# misc.net
KiCad netlist of a schematic drawn in Altium Designer
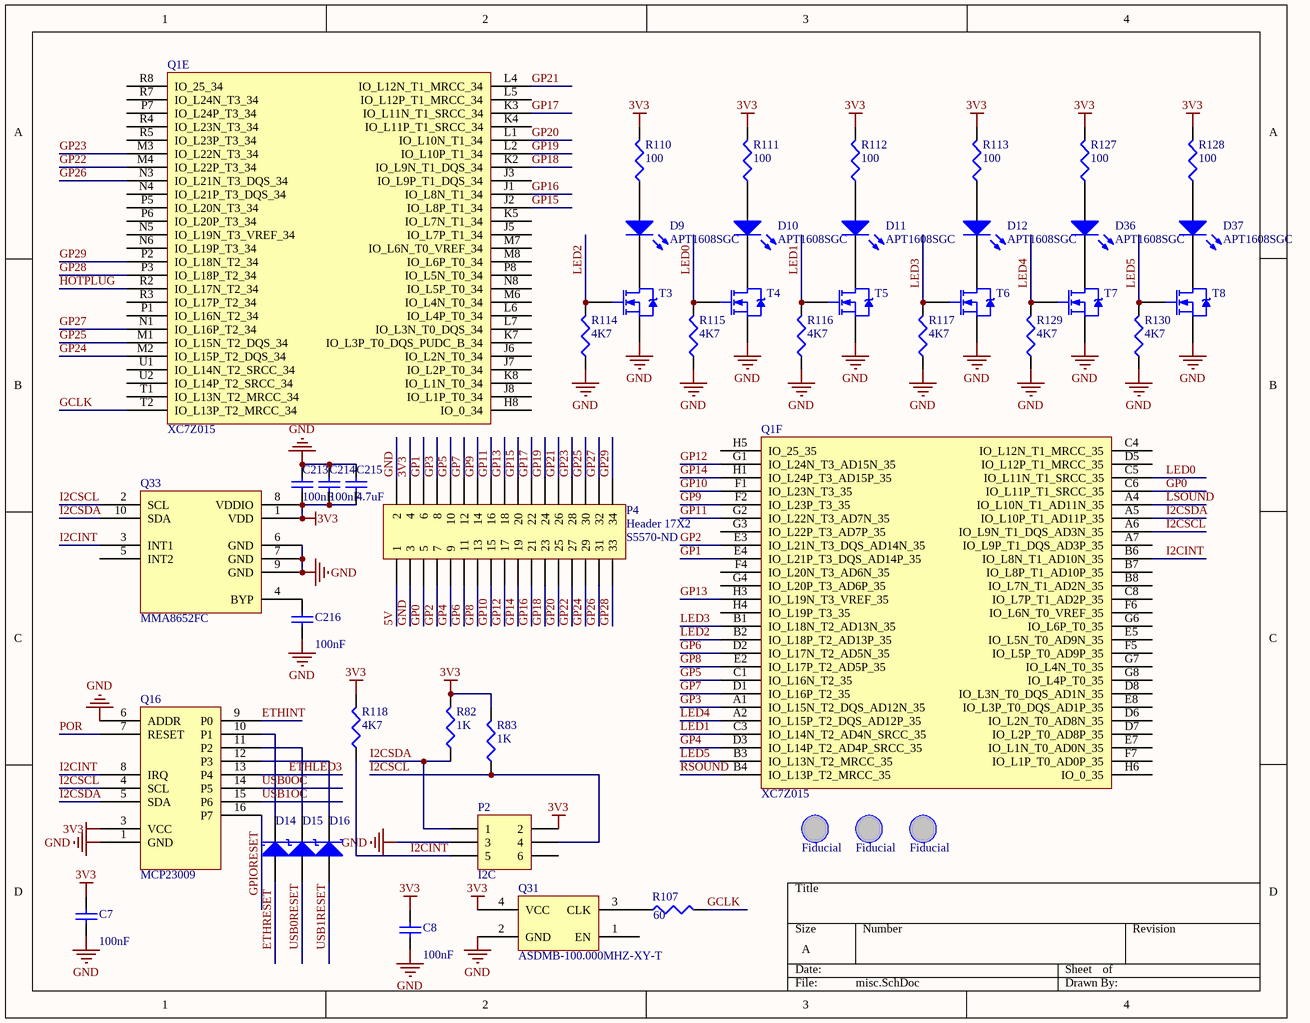
[diagram p0: misc.SchDoc]

(export (version "E")
  (design (tool "Eeschema 10.0.6"))
  (components
    (comp (ref "C7")
      (value "100nF")
      (footprint "CAPC1005X06L")
      (description "Capacitor")
      (fields (field (name "Comment") "Cap") (field (name "PUBLISHER") "Altium Limited"))
      (libsource (lib "Miscellaneous Devices") (part "Cap"))
    )
    (comp (ref "C8")
      (value "100nF")
      (footprint "CAPC1005X06L")
      (description "Capacitor")
      (fields (field (name "Comment") "Cap") (field (name "PUBLISHER") "Altium Limited"))
      (libsource (lib "Miscellaneous Devices") (part "Cap"))
    )
    (comp (ref "C213")
      (value "100nF")
      (footprint "CAPC1005X06L")
      (description "Capacitor")
      (fields (field (name "Comment") "Cap") (field (name "PUBLISHER") "Altium Limited"))
      (libsource (lib "Miscellaneous Devices") (part "Cap"))
    )
    (comp (ref "C214")
      (value "100nF")
      (footprint "CAPC1005X06L")
      (description "Capacitor")
      (fields (field (name "Comment") "Cap") (field (name "PUBLISHER") "Altium Limited"))
      (libsource (lib "Miscellaneous Devices") (part "Cap"))
    )
    (comp (ref "C215")
      (value "4.7uF")
      (footprint "CAPC1608X90N")
      (description "Capacitor")
      (fields (field (name "Comment") "GRM188R60J475ME19D") (field (name "PUBLISHER") "Altium Limited"))
      (libsource (lib "Miscellaneous Devices") (part "Cap"))
    )
    (comp (ref "C216")
      (value "100nF")
      (footprint "CAPC1005X06L")
      (description "Capacitor")
      (fields (field (name "Comment") "Cap") (field (name "PUBLISHER") "Altium Limited"))
      (libsource (lib "Miscellaneous Devices") (part "Cap"))
    )
    (comp (ref "D9")
      (value "APT1608SGC")
      (footprint "LED-0603")
      (description "Typical RED, GREEN, YELLOW, AMBER GaAs LED")
      (fields (field (name "PUBLISHER") "Altium Limited"))
      (libsource (lib "Miscellaneous Devices") (part "LED2"))
    )
    (comp (ref "D10")
      (value "APT1608SGC")
      (footprint "LED-0603")
      (description "Typical RED, GREEN, YELLOW, AMBER GaAs LED")
      (fields (field (name "PUBLISHER") "Altium Limited"))
      (libsource (lib "Miscellaneous Devices") (part "LED2"))
    )
    (comp (ref "D11")
      (value "APT1608SGC")
      (footprint "LED-0603")
      (description "Typical RED, GREEN, YELLOW, AMBER GaAs LED")
      (fields (field (name "PUBLISHER") "Altium Limited"))
      (libsource (lib "Miscellaneous Devices") (part "LED2"))
    )
    (comp (ref "D12")
      (value "APT1608SGC")
      (footprint "LED-0603")
      (description "Typical RED, GREEN, YELLOW, AMBER GaAs LED")
      (fields (field (name "PUBLISHER") "Altium Limited"))
      (libsource (lib "Miscellaneous Devices") (part "LED2"))
    )
    (comp (ref "D14")
      (value "BAT54FSCT-ND")
      (footprint "BAT54")
      (description "Schottky Diode")
      (fields (field (name "PUBLISHER") "Altium Limited"))
      (libsource (lib "Miscellaneous Devices") (part "D Schottky"))
    )
    (comp (ref "D15")
      (value "BAT54FSCT-ND")
      (footprint "BAT54")
      (description "Schottky Diode")
      (fields (field (name "PUBLISHER") "Altium Limited"))
      (libsource (lib "Miscellaneous Devices") (part "D Schottky"))
    )
    (comp (ref "D16")
      (value "BAT54FSCT-ND")
      (footprint "BAT54")
      (description "Schottky Diode")
      (fields (field (name "PUBLISHER") "Altium Limited"))
      (libsource (lib "Miscellaneous Devices") (part "D Schottky"))
    )
    (comp (ref "D36")
      (value "APT1608SGC")
      (footprint "LED-0603")
      (description "Typical RED, GREEN, YELLOW, AMBER GaAs LED")
      (fields (field (name "PUBLISHER") "Altium Limited"))
      (libsource (lib "Miscellaneous Devices") (part "LED2"))
    )
    (comp (ref "D37")
      (value "APT1608SGC")
      (footprint "LED-0603")
      (description "Typical RED, GREEN, YELLOW, AMBER GaAs LED")
      (fields (field (name "PUBLISHER") "Altium Limited"))
      (libsource (lib "Miscellaneous Devices") (part "LED2"))
    )
    (comp (ref "FIDU1") (value "Fiducial") (footprint "FIDU") (libsource (lib "schlib") (part "FIDU")))
    (comp (ref "FIDU2") (value "Fiducial") (footprint "FIDU") (libsource (lib "schlib") (part "FIDU")))
    (comp (ref "FIDU3") (value "Fiducial") (footprint "FIDU") (libsource (lib "schlib") (part "FIDU")))
    (comp (ref "P2")
      (value "I2C")
      (footprint "HDR2X3")
      (description "Header, 3-Pin, Dual row")
      (fields (field (name "PUBLISHER") "Altium Limited"))
      (libsource (lib "Miscellaneous Connectors") (part "Header 3X2"))
    )
    (comp (ref "P4")
      (value "Header 17X2")
      (footprint "HDR2X17")
      (description "Header, 17-Pin, Dual row")
      (fields (field (name "SUPPLIER PART NUMBER 1") "S5570-ND") (field (name "PUBLISHER") "Altium Limited"))
      (libsource (lib "Miscellaneous Connectors") (part "Header 17X2"))
    )
    (comp (ref "Q1") (value "XC7Z015") (footprint "BGA484x22") (libsource (lib "schlib") (part "XC7Z015")))
    (comp (ref "Q16") (value "MCP23009") (footprint "MCP23009") (libsource (lib "schlib") (part "MCP23009")))
    (comp (ref "Q31")
      (value "ASDMB-100.000MHZ-XY-T")
      (footprint "ASDMB")
      (libsource (lib "schlib") (part "osc"))
    )
    (comp (ref "Q33")
      (value "MMA8652FC")
      (footprint "MMA8653FC")
      (libsource (lib "schlib") (part "MMA8652FC"))
    )
    (comp (ref "R82")
      (value "1K")
      (footprint "J1-0603")
      (description "Resistor")
      (fields (field (name "Comment") "RC1608J102CS") (field (name "PUBLISHER") "Altium Limited"))
      (libsource (lib "Miscellaneous Devices") (part "Res3"))
    )
    (comp (ref "R83")
      (value "1K")
      (footprint "J1-0603")
      (description "Resistor")
      (fields (field (name "Comment") "RC1608J102CS") (field (name "PUBLISHER") "Altium Limited"))
      (libsource (lib "Miscellaneous Devices") (part "Res3"))
    )
    (comp (ref "R107")
      (value "60")
      (footprint "J1-0603")
      (description "Resistor")
      (fields (field (name "Comment") "RC1608F60R4CS"))
      (libsource (lib "Miscellaneous Devices") (part "Res3"))
    )
    (comp (ref "R110")
      (value "100")
      (footprint "J1-0603")
      (description "Resistor")
      (fields (field (name "Comment") "RC1608F101CS"))
      (libsource (lib "Miscellaneous Devices") (part "Res3"))
    )
    (comp (ref "R111")
      (value "100")
      (footprint "J1-0603")
      (description "Resistor")
      (fields (field (name "Comment") "RC1608F101CS"))
      (libsource (lib "Miscellaneous Devices") (part "Res3"))
    )
    (comp (ref "R112")
      (value "100")
      (footprint "J1-0603")
      (description "Resistor")
      (fields (field (name "Comment") "RC1608F101CS"))
      (libsource (lib "Miscellaneous Devices") (part "Res3"))
    )
    (comp (ref "R113")
      (value "100")
      (footprint "J1-0603")
      (description "Resistor")
      (fields (field (name "Comment") "RC1608F101CS"))
      (libsource (lib "Miscellaneous Devices") (part "Res3"))
    )
    (comp (ref "R114")
      (value "4K7")
      (footprint "J1-0603")
      (description "Resistor")
      (fields (field (name "Comment") "RC1608J472CS"))
      (libsource (lib "Miscellaneous Devices") (part "Res3"))
    )
    (comp (ref "R115")
      (value "4K7")
      (footprint "J1-0603")
      (description "Resistor")
      (fields (field (name "Comment") "RC1608J472CS"))
      (libsource (lib "Miscellaneous Devices") (part "Res3"))
    )
    (comp (ref "R116")
      (value "4K7")
      (footprint "J1-0603")
      (description "Resistor")
      (fields (field (name "Comment") "RC1608J472CS"))
      (libsource (lib "Miscellaneous Devices") (part "Res3"))
    )
    (comp (ref "R117")
      (value "4K7")
      (footprint "J1-0603")
      (description "Resistor")
      (fields (field (name "Comment") "RC1608J472CS"))
      (libsource (lib "Miscellaneous Devices") (part "Res3"))
    )
    (comp (ref "R118")
      (value "4K7")
      (footprint "J1-0603")
      (description "Resistor")
      (fields (field (name "Comment") "RC1608J472CS"))
      (libsource (lib "Miscellaneous Devices") (part "Res3"))
    )
    (comp (ref "R127")
      (value "100")
      (footprint "J1-0603")
      (description "Resistor")
      (fields (field (name "Comment") "RC1608F101CS"))
      (libsource (lib "Miscellaneous Devices") (part "Res3"))
    )
    (comp (ref "R128")
      (value "100")
      (footprint "J1-0603")
      (description "Resistor")
      (fields (field (name "Comment") "RC1608F101CS"))
      (libsource (lib "Miscellaneous Devices") (part "Res3"))
    )
    (comp (ref "R129")
      (value "4K7")
      (footprint "J1-0603")
      (description "Resistor")
      (fields (field (name "Comment") "RC1608J472CS"))
      (libsource (lib "Miscellaneous Devices") (part "Res3"))
    )
    (comp (ref "R130")
      (value "4K7")
      (footprint "J1-0603")
      (description "Resistor")
      (fields (field (name "Comment") "RC1608J472CS"))
      (libsource (lib "Miscellaneous Devices") (part "Res3"))
    )
    (comp (ref "T3")
      (value "~")
      (footprint "EMT3F")
      (description "N-Channel Power MOSFET")
      (fields (field (name "PUBLISHER") "Altium Limited"))
      (libsource (lib "Miscellaneous Devices") (part "NMOS-2"))
    )
    (comp (ref "T4")
      (value "~")
      (footprint "EMT3F")
      (description "N-Channel Power MOSFET")
      (fields (field (name "PUBLISHER") "Altium Limited"))
      (libsource (lib "Miscellaneous Devices") (part "NMOS-2"))
    )
    (comp (ref "T5")
      (value "~")
      (footprint "EMT3F")
      (description "N-Channel Power MOSFET")
      (fields (field (name "PUBLISHER") "Altium Limited"))
      (libsource (lib "Miscellaneous Devices") (part "NMOS-2"))
    )
    (comp (ref "T6")
      (value "~")
      (footprint "EMT3F")
      (description "N-Channel Power MOSFET")
      (fields (field (name "PUBLISHER") "Altium Limited"))
      (libsource (lib "Miscellaneous Devices") (part "NMOS-2"))
    )
    (comp (ref "T7")
      (value "~")
      (footprint "EMT3F")
      (description "N-Channel Power MOSFET")
      (fields (field (name "PUBLISHER") "Altium Limited"))
      (libsource (lib "Miscellaneous Devices") (part "NMOS-2"))
    )
    (comp (ref "T8")
      (value "~")
      (footprint "EMT3F")
      (description "N-Channel Power MOSFET")
      (fields (field (name "PUBLISHER") "Altium Limited"))
      (libsource (lib "Miscellaneous Devices") (part "NMOS-2"))
    )
  )
  (nets
    (net (code "1") (name "/5V") (class "Default")
      (node (ref "P4") (pin "1") (pinfunction "1_1") (pintype "passive"))
    )
    (net (code "2") (name "/ETHINT") (class "Default")
      (node (ref "Q16") (pin "9") (pinfunction "P0_9") (pintype "passive"))
    )
    (net (code "3") (name "/ETHLED3") (class "Default")
      (node (ref "Q16") (pin "13") (pinfunction "P4_13") (pintype "passive"))
    )
    (net (code "4") (name "/ETHRESET") (class "Default")
      (node (ref "D14") (pin "1") (pinfunction "A_1") (pintype "passive"))
    )
    (net (code "5") (name "/GCLK") (class "Default")
      (node (ref "Q1") (pin "T2") (pinfunction "IO_L13P_T2_MRCC_34_T2") (pintype "passive"))
      (node (ref "R107") (pin "2") (pinfunction "2_2") (pintype "passive"))
    )
    (net (code "6") (name "/GP0") (class "Default")
      (node (ref "P4") (pin "5") (pinfunction "5_5") (pintype "passive"))
      (node (ref "Q1") (pin "C6") (pinfunction "IO_L11P_T1_SRCC_35_C6") (pintype "passive"))
    )
    (net (code "7") (name "/GP1") (class "Default")
      (node (ref "P4") (pin "6") (pinfunction "6_6") (pintype "passive"))
      (node (ref "Q1") (pin "E4") (pinfunction "IO_L21P_T3_DQS_AD14P_35_E4") (pintype "passive"))
    )
    (net (code "8") (name "/GP2") (class "Default")
      (node (ref "P4") (pin "7") (pinfunction "7_7") (pintype "passive"))
      (node (ref "Q1") (pin "E3") (pinfunction "IO_L21N_T3_DQS_AD14N_35_E3") (pintype "passive"))
    )
    (net (code "9") (name "/GP3") (class "Default")
      (node (ref "P4") (pin "8") (pinfunction "8_8") (pintype "passive"))
      (node (ref "Q1") (pin "A1") (pinfunction "IO_L15N_T2_DQS_AD12N_35_A1") (pintype "passive"))
    )
    (net (code "10") (name "/GP4") (class "Default")
      (node (ref "P4") (pin "9") (pinfunction "9_9") (pintype "passive"))
      (node (ref "Q1") (pin "D3") (pinfunction "IO_L14P_T2_AD4P_SRCC_35_D3") (pintype "passive"))
    )
    (net (code "11") (name "/GP5") (class "Default")
      (node (ref "P4") (pin "10") (pinfunction "10_10") (pintype "passive"))
      (node (ref "Q1") (pin "C1") (pinfunction "IO_L16N_T2_35_C1") (pintype "passive"))
    )
    (net (code "12") (name "/GP6") (class "Default")
      (node (ref "P4") (pin "11") (pinfunction "11_11") (pintype "passive"))
      (node (ref "Q1") (pin "D2") (pinfunction "IO_L17N_T2_AD5N_35_D2") (pintype "passive"))
    )
    (net (code "13") (name "/GP7") (class "Default")
      (node (ref "P4") (pin "12") (pinfunction "12_12") (pintype "passive"))
      (node (ref "Q1") (pin "D1") (pinfunction "IO_L16P_T2_35_D1") (pintype "passive"))
    )
    (net (code "14") (name "/GP8") (class "Default")
      (node (ref "P4") (pin "13") (pinfunction "13_13") (pintype "passive"))
      (node (ref "Q1") (pin "E2") (pinfunction "IO_L17P_T2_AD5P_35_E2") (pintype "passive"))
    )
    (net (code "15") (name "/GP9") (class "Default")
      (node (ref "P4") (pin "14") (pinfunction "14_14") (pintype "passive"))
      (node (ref "Q1") (pin "F2") (pinfunction "IO_L23P_T3_35_F2") (pintype "passive"))
    )
    (net (code "16") (name "/GP10") (class "Default")
      (node (ref "P4") (pin "15") (pinfunction "15_15") (pintype "passive"))
      (node (ref "Q1") (pin "F1") (pinfunction "IO_L23N_T3_35_F1") (pintype "passive"))
    )
    (net (code "17") (name "/GP11") (class "Default")
      (node (ref "P4") (pin "16") (pinfunction "16_16") (pintype "passive"))
      (node (ref "Q1") (pin "G2") (pinfunction "IO_L22N_T3_AD7N_35_G2") (pintype "passive"))
    )
    (net (code "18") (name "/GP12") (class "Default")
      (node (ref "P4") (pin "17") (pinfunction "17_17") (pintype "passive"))
      (node (ref "Q1") (pin "G1") (pinfunction "IO_L24N_T3_AD15N_35_G1") (pintype "passive"))
    )
    (net (code "19") (name "/GP13") (class "Default")
      (node (ref "P4") (pin "18") (pinfunction "18_18") (pintype "passive"))
      (node (ref "Q1") (pin "H3") (pinfunction "IO_L19N_T3_VREF_35_H3") (pintype "passive"))
    )
    (net (code "20") (name "/GP14") (class "Default")
      (node (ref "P4") (pin "19") (pinfunction "19_19") (pintype "passive"))
      (node (ref "Q1") (pin "H1") (pinfunction "IO_L24P_T3_AD15P_35_H1") (pintype "passive"))
    )
    (net (code "21") (name "/GP15") (class "Default")
      (node (ref "P4") (pin "20") (pinfunction "20_20") (pintype "passive"))
      (node (ref "Q1") (pin "J2") (pinfunction "IO_L8P_T1_34_J2") (pintype "passive"))
    )
    (net (code "22") (name "/GP16") (class "Default")
      (node (ref "P4") (pin "21") (pinfunction "21_21") (pintype "passive"))
      (node (ref "Q1") (pin "J1") (pinfunction "IO_L8N_T1_34_J1") (pintype "passive"))
    )
    (net (code "23") (name "/GP17") (class "Default")
      (node (ref "P4") (pin "22") (pinfunction "22_22") (pintype "passive"))
      (node (ref "Q1") (pin "K3") (pinfunction "IO_L11N_T1_SRCC_34_K3") (pintype "passive"))
    )
    (net (code "24") (name "/GP18") (class "Default")
      (node (ref "P4") (pin "23") (pinfunction "23_23") (pintype "passive"))
      (node (ref "Q1") (pin "K2") (pinfunction "IO_L9N_T1_DQS_34_K2") (pintype "passive"))
    )
    (net (code "25") (name "/GP19") (class "Default")
      (node (ref "P4") (pin "24") (pinfunction "24_24") (pintype "passive"))
      (node (ref "Q1") (pin "L2") (pinfunction "IO_L10P_T1_34_L2") (pintype "passive"))
    )
    (net (code "26") (name "/GP20") (class "Default")
      (node (ref "P4") (pin "25") (pinfunction "25_25") (pintype "passive"))
      (node (ref "Q1") (pin "L1") (pinfunction "IO_L10N_T1_34_L1") (pintype "passive"))
    )
    (net (code "27") (name "/GP21") (class "Default")
      (node (ref "P4") (pin "26") (pinfunction "26_26") (pintype "passive"))
      (node (ref "Q1") (pin "L4") (pinfunction "IO_L12N_T1_MRCC_34_L4") (pintype "passive"))
    )
    (net (code "28") (name "/GP22") (class "Default")
      (node (ref "P4") (pin "27") (pinfunction "27_27") (pintype "passive"))
      (node (ref "Q1") (pin "M4") (pinfunction "IO_L22P_T3_34_M4") (pintype "passive"))
    )
    (net (code "29") (name "/GP23") (class "Default")
      (node (ref "P4") (pin "28") (pinfunction "28_28") (pintype "passive"))
      (node (ref "Q1") (pin "M3") (pinfunction "IO_L22N_T3_34_M3") (pintype "passive"))
    )
    (net (code "30") (name "/GP24") (class "Default")
      (node (ref "P4") (pin "29") (pinfunction "29_29") (pintype "passive"))
      (node (ref "Q1") (pin "M2") (pinfunction "IO_L15P_T2_DQS_34_M2") (pintype "passive"))
    )
    (net (code "31") (name "/GP25") (class "Default")
      (node (ref "P4") (pin "30") (pinfunction "30_30") (pintype "passive"))
      (node (ref "Q1") (pin "M1") (pinfunction "IO_L15N_T2_DQS_34_M1") (pintype "passive"))
    )
    (net (code "32") (name "/GP26") (class "Default")
      (node (ref "P4") (pin "31") (pinfunction "31_31") (pintype "passive"))
      (node (ref "Q1") (pin "N3") (pinfunction "IO_L21N_T3_DQS_34_N3") (pintype "passive"))
    )
    (net (code "33") (name "/GP27") (class "Default")
      (node (ref "P4") (pin "32") (pinfunction "32_32") (pintype "passive"))
      (node (ref "Q1") (pin "N1") (pinfunction "IO_L16P_T2_34_N1") (pintype "passive"))
    )
    (net (code "34") (name "/GP28") (class "Default")
      (node (ref "P4") (pin "33") (pinfunction "33_33") (pintype "passive"))
      (node (ref "Q1") (pin "P3") (pinfunction "IO_L18P_T2_34_P3") (pintype "passive"))
    )
    (net (code "35") (name "/GP29") (class "Default")
      (node (ref "P4") (pin "34") (pinfunction "34_34") (pintype "passive"))
      (node (ref "Q1") (pin "P2") (pinfunction "IO_L18N_T2_34_P2") (pintype "passive"))
    )
    (net (code "36") (name "/GPIORESET") (class "Default")
      (node (ref "Q16") (pin "16") (pinfunction "P7_16") (pintype "passive"))
    )
    (net (code "37") (name "/HOTPLUG") (class "Default")
      (node (ref "Q1") (pin "R2") (pinfunction "IO_L17N_T2_34_R2") (pintype "passive"))
    )
    (net (code "38") (name "/I2CINT") (class "Default")
      (node (ref "P2") (pin "5") (pinfunction "5_5") (pintype "passive"))
      (node (ref "Q1") (pin "B6") (pinfunction "IO_L8N_T1_AD10N_35_B6") (pintype "passive"))
      (node (ref "Q16") (pin "8") (pinfunction "IRQ_8") (pintype "passive"))
      (node (ref "Q33") (pin "3") (pinfunction "INT1_3") (pintype "passive"))
      (node (ref "R118") (pin "1") (pinfunction "1_1") (pintype "passive"))
    )
    (net (code "39") (name "/I2CSCL") (class "Default")
      (node (ref "P2") (pin "4") (pinfunction "4_4") (pintype "passive"))
      (node (ref "Q1") (pin "A6") (pinfunction "IO_L9N_T1_DQS_AD3N_35_A6") (pintype "passive"))
      (node (ref "Q16") (pin "4") (pinfunction "SCL_4") (pintype "passive"))
      (node (ref "Q33") (pin "2") (pinfunction "SCL_2") (pintype "passive"))
      (node (ref "R83") (pin "1") (pinfunction "1_1") (pintype "passive"))
    )
    (net (code "40") (name "/I2CSDA") (class "Default")
      (node (ref "P2") (pin "1") (pinfunction "1_1") (pintype "passive"))
      (node (ref "Q1") (pin "A5") (pinfunction "IO_L10P_T1_AD11P_35_A5") (pintype "passive"))
      (node (ref "Q16") (pin "5") (pinfunction "SDA_5") (pintype "passive"))
      (node (ref "Q33") (pin "10") (pinfunction "SDA_10") (pintype "passive"))
      (node (ref "R82") (pin "1") (pinfunction "1_1") (pintype "passive"))
    )
    (net (code "41") (name "/LED0") (class "Default")
      (node (ref "Q1") (pin "C5") (pinfunction "IO_L11N_T1_SRCC_35_C5") (pintype "passive"))
      (node (ref "R115") (pin "2") (pinfunction "2_2") (pintype "passive"))
      (node (ref "T4") (pin "1") (pinfunction "G_1") (pintype "passive"))
    )
    (net (code "42") (name "/LED1") (class "Default")
      (node (ref "Q1") (pin "C3") (pinfunction "IO_L14N_T2_AD4N_SRCC_35_C3") (pintype "passive"))
      (node (ref "R116") (pin "2") (pinfunction "2_2") (pintype "passive"))
      (node (ref "T5") (pin "1") (pinfunction "G_1") (pintype "passive"))
    )
    (net (code "43") (name "/LED2") (class "Default")
      (node (ref "Q1") (pin "B2") (pinfunction "IO_L18P_T2_AD13P_35_B2") (pintype "passive"))
      (node (ref "R114") (pin "2") (pinfunction "2_2") (pintype "passive"))
      (node (ref "T3") (pin "1") (pinfunction "G_1") (pintype "passive"))
    )
    (net (code "44") (name "/LED3") (class "Default")
      (node (ref "Q1") (pin "B1") (pinfunction "IO_L18N_T2_AD13N_35_B1") (pintype "passive"))
      (node (ref "R117") (pin "2") (pinfunction "2_2") (pintype "passive"))
      (node (ref "T6") (pin "1") (pinfunction "G_1") (pintype "passive"))
    )
    (net (code "45") (name "/LED4") (class "Default")
      (node (ref "Q1") (pin "A2") (pinfunction "IO_L15P_T2_DQS_AD12P_35_A2") (pintype "passive"))
      (node (ref "R129") (pin "2") (pinfunction "2_2") (pintype "passive"))
      (node (ref "T7") (pin "1") (pinfunction "G_1") (pintype "passive"))
    )
    (net (code "46") (name "/LED5") (class "Default")
      (node (ref "Q1") (pin "B3") (pinfunction "IO_L13N_T2_MRCC_35_B3") (pintype "passive"))
      (node (ref "R130") (pin "2") (pinfunction "2_2") (pintype "passive"))
      (node (ref "T8") (pin "1") (pinfunction "G_1") (pintype "passive"))
    )
    (net (code "47") (name "/LSOUND") (class "Default")
      (node (ref "Q1") (pin "A4") (pinfunction "IO_L10N_T1_AD11N_35_A4") (pintype "passive"))
    )
    (net (code "48") (name "/POR") (class "Default")
      (node (ref "Q16") (pin "7") (pinfunction "RESET_7") (pintype "passive"))
    )
    (net (code "49") (name "/RSOUND") (class "Default")
      (node (ref "Q1") (pin "B4") (pinfunction "IO_L13P_T2_MRCC_35_B4") (pintype "passive"))
    )
    (net (code "50") (name "/USB0OC") (class "Default")
      (node (ref "Q16") (pin "14") (pinfunction "P5_14") (pintype "passive"))
    )
    (net (code "51") (name "/USB0RESET") (class "Default")
      (node (ref "D15") (pin "1") (pinfunction "A_1") (pintype "passive"))
    )
    (net (code "52") (name "/USB1OC") (class "Default")
      (node (ref "Q16") (pin "15") (pinfunction "P6_15") (pintype "passive"))
    )
    (net (code "53") (name "/USB1RESET") (class "Default")
      (node (ref "D16") (pin "1") (pinfunction "A_1") (pintype "passive"))
    )
    (net (code "54") (name "3V3") (class "Default")
      (node (ref "C213") (pin "2") (pinfunction "2_2") (pintype "passive"))
      (node (ref "C214") (pin "1") (pinfunction "1_1") (pintype "passive"))
      (node (ref "C215") (pin "1") (pinfunction "1_1") (pintype "passive"))
      (node (ref "C7") (pin "2") (pinfunction "2_2") (pintype "passive"))
      (node (ref "C8") (pin "2") (pinfunction "2_2") (pintype "passive"))
      (node (ref "P2") (pin "2") (pinfunction "2_2") (pintype "passive"))
      (node (ref "P4") (pin "4") (pinfunction "4_4") (pintype "passive"))
      (node (ref "Q16") (pin "3") (pinfunction "VCC_3") (pintype "passive"))
      (node (ref "Q31") (pin "4") (pinfunction "VCC_4") (pintype "passive"))
      (node (ref "Q33") (pin "1") (pinfunction "VDD_1") (pintype "passive"))
      (node (ref "Q33") (pin "8") (pinfunction "VDDIO_8") (pintype "passive"))
      (node (ref "R110") (pin "2") (pinfunction "2_2") (pintype "passive"))
      (node (ref "R111") (pin "2") (pinfunction "2_2") (pintype "passive"))
      (node (ref "R112") (pin "2") (pinfunction "2_2") (pintype "passive"))
      (node (ref "R113") (pin "2") (pinfunction "2_2") (pintype "passive"))
      (node (ref "R118") (pin "2") (pinfunction "2_2") (pintype "passive"))
      (node (ref "R127") (pin "2") (pinfunction "2_2") (pintype "passive"))
      (node (ref "R128") (pin "2") (pinfunction "2_2") (pintype "passive"))
      (node (ref "R82") (pin "2") (pinfunction "2_2") (pintype "passive"))
      (node (ref "R83") (pin "2") (pinfunction "2_2") (pintype "passive"))
    )
    (net (code "55") (name "GND") (class "Default")
      (node (ref "C213") (pin "1") (pinfunction "1_1") (pintype "passive"))
      (node (ref "C214") (pin "2") (pinfunction "2_2") (pintype "passive"))
      (node (ref "C215") (pin "2") (pinfunction "2_2") (pintype "passive"))
      (node (ref "C216") (pin "1") (pinfunction "1_1") (pintype "passive"))
      (node (ref "C7") (pin "1") (pinfunction "1_1") (pintype "passive"))
      (node (ref "C8") (pin "1") (pinfunction "1_1") (pintype "passive"))
      (node (ref "P2") (pin "3") (pinfunction "3_3") (pintype "passive"))
      (node (ref "P4") (pin "2") (pinfunction "2_2") (pintype "passive"))
      (node (ref "P4") (pin "3") (pinfunction "3_3") (pintype "passive"))
      (node (ref "Q16") (pin "1") (pinfunction "GND_1") (pintype "passive"))
      (node (ref "Q16") (pin "6") (pinfunction "ADDR_6") (pintype "passive"))
      (node (ref "Q31") (pin "2") (pinfunction "GND_2") (pintype "passive"))
      (node (ref "Q33") (pin "6") (pinfunction "GND_6") (pintype "passive"))
      (node (ref "Q33") (pin "7") (pinfunction "GND_7") (pintype "passive"))
      (node (ref "Q33") (pin "9") (pinfunction "GND_9") (pintype "passive"))
      (node (ref "R114") (pin "1") (pinfunction "1_1") (pintype "passive"))
      (node (ref "R115") (pin "1") (pinfunction "1_1") (pintype "passive"))
      (node (ref "R116") (pin "1") (pinfunction "1_1") (pintype "passive"))
      (node (ref "R117") (pin "1") (pinfunction "1_1") (pintype "passive"))
      (node (ref "R129") (pin "1") (pinfunction "1_1") (pintype "passive"))
      (node (ref "R130") (pin "1") (pinfunction "1_1") (pintype "passive"))
      (node (ref "T3") (pin "2") (pinfunction "S_2") (pintype "passive"))
      (node (ref "T4") (pin "2") (pinfunction "S_2") (pintype "passive"))
      (node (ref "T5") (pin "2") (pinfunction "S_2") (pintype "passive"))
      (node (ref "T6") (pin "2") (pinfunction "S_2") (pintype "passive"))
      (node (ref "T7") (pin "2") (pinfunction "S_2") (pintype "passive"))
      (node (ref "T8") (pin "2") (pinfunction "S_2") (pintype "passive"))
    )
    (net (code "56") (name "Net-(D9-PadA)") (class "Default")
      (node (ref "D9") (pin "A") (pinfunction "A_A") (pintype "passive"))
      (node (ref "R110") (pin "1") (pinfunction "1_1") (pintype "passive"))
    )
    (net (code "57") (name "Net-(D10-PadA)") (class "Default")
      (node (ref "D10") (pin "A") (pinfunction "A_A") (pintype "passive"))
      (node (ref "R111") (pin "1") (pinfunction "1_1") (pintype "passive"))
    )
    (net (code "58") (name "Net-(D11-PadA)") (class "Default")
      (node (ref "D11") (pin "A") (pinfunction "A_A") (pintype "passive"))
      (node (ref "R112") (pin "1") (pinfunction "1_1") (pintype "passive"))
    )
    (net (code "59") (name "Net-(D12-PadA)") (class "Default")
      (node (ref "D12") (pin "A") (pinfunction "A_A") (pintype "passive"))
      (node (ref "R113") (pin "1") (pinfunction "1_1") (pintype "passive"))
    )
    (net (code "60") (name "Net-(D14-K)") (class "Default")
      (node (ref "D14") (pin "2") (pinfunction "K_2") (pintype "passive"))
      (node (ref "Q16") (pin "10") (pinfunction "P1_10") (pintype "passive"))
    )
    (net (code "61") (name "Net-(D15-K)") (class "Default")
      (node (ref "D15") (pin "2") (pinfunction "K_2") (pintype "passive"))
      (node (ref "Q16") (pin "11") (pinfunction "P2_11") (pintype "passive"))
    )
    (net (code "62") (name "Net-(D16-K)") (class "Default")
      (node (ref "D16") (pin "2") (pinfunction "K_2") (pintype "passive"))
      (node (ref "Q16") (pin "12") (pinfunction "P3_12") (pintype "passive"))
    )
    (net (code "63") (name "Net-(D36-PadA)") (class "Default")
      (node (ref "D36") (pin "A") (pinfunction "A_A") (pintype "passive"))
      (node (ref "R127") (pin "1") (pinfunction "1_1") (pintype "passive"))
    )
    (net (code "64") (name "Net-(D37-PadA)") (class "Default")
      (node (ref "D37") (pin "A") (pinfunction "A_A") (pintype "passive"))
      (node (ref "R128") (pin "1") (pinfunction "1_1") (pintype "passive"))
    )
    (net (code "65") (name "Net-(Q31-CLK)") (class "Default")
      (node (ref "Q31") (pin "3") (pinfunction "CLK_3") (pintype "passive"))
      (node (ref "R107") (pin "1") (pinfunction "1_1") (pintype "passive"))
    )
    (net (code "66") (name "Net-(Q33-BYP)") (class "Default")
      (node (ref "C216") (pin "2") (pinfunction "2_2") (pintype "passive"))
      (node (ref "Q33") (pin "4") (pinfunction "BYP_4") (pintype "passive"))
    )
    (net (code "67") (name "Net-(T3-D)") (class "Default")
      (node (ref "D9") (pin "K") (pinfunction "K_K") (pintype "passive"))
      (node (ref "T3") (pin "3") (pinfunction "D_3") (pintype "passive"))
    )
    (net (code "68") (name "Net-(T4-D)") (class "Default")
      (node (ref "D10") (pin "K") (pinfunction "K_K") (pintype "passive"))
      (node (ref "T4") (pin "3") (pinfunction "D_3") (pintype "passive"))
    )
    (net (code "69") (name "Net-(T5-D)") (class "Default")
      (node (ref "D11") (pin "K") (pinfunction "K_K") (pintype "passive"))
      (node (ref "T5") (pin "3") (pinfunction "D_3") (pintype "passive"))
    )
    (net (code "70") (name "Net-(T6-D)") (class "Default")
      (node (ref "D12") (pin "K") (pinfunction "K_K") (pintype "passive"))
      (node (ref "T6") (pin "3") (pinfunction "D_3") (pintype "passive"))
    )
    (net (code "71") (name "Net-(T7-D)") (class "Default")
      (node (ref "D36") (pin "K") (pinfunction "K_K") (pintype "passive"))
      (node (ref "T7") (pin "3") (pinfunction "D_3") (pintype "passive"))
    )
    (net (code "72") (name "Net-(T8-D)") (class "Default")
      (node (ref "D37") (pin "K") (pinfunction "K_K") (pintype "passive"))
      (node (ref "T8") (pin "3") (pinfunction "D_3") (pintype "passive"))
    )
    (net (code "73") (name "unconnected-(P2-Pad6)") (class "Default")
      (node (ref "P2") (pin "6") (pinfunction "6_6") (pintype "passive"))
    )
    (net (code "74") (name "unconnected-(Q1E-IO_0_34-PadH8)") (class "Default")
      (node (ref "Q1") (pin "H8") (pinfunction "IO_0_34_H8") (pintype "passive"))
    )
    (net (code "75") (name "unconnected-(Q1E-IO_25_34-PadR8)") (class "Default")
      (node (ref "Q1") (pin "R8") (pinfunction "IO_25_34_R8") (pintype "passive"))
    )
    (net (code "76") (name "unconnected-(Q1E-IO_L1N_T0_34-PadK8)") (class "Default")
      (node (ref "Q1") (pin "K8") (pinfunction "IO_L1N_T0_34_K8") (pintype "passive"))
    )
    (net (code "77") (name "unconnected-(Q1E-IO_L1P_T0_34-PadJ8)") (class "Default")
      (node (ref "Q1") (pin "J8") (pinfunction "IO_L1P_T0_34_J8") (pintype "passive"))
    )
    (net (code "78") (name "unconnected-(Q1E-IO_L2N_T0_34-PadJ6)") (class "Default")
      (node (ref "Q1") (pin "J6") (pinfunction "IO_L2N_T0_34_J6") (pintype "passive"))
    )
    (net (code "79") (name "unconnected-(Q1E-IO_L2P_T0_34-PadJ7)") (class "Default")
      (node (ref "Q1") (pin "J7") (pinfunction "IO_L2P_T0_34_J7") (pintype "passive"))
    )
    (net (code "80") (name "unconnected-(Q1E-IO_L3N_T0_DQS_34-PadL7)") (class "Default")
      (node (ref "Q1") (pin "L7") (pinfunction "IO_L3N_T0_DQS_34_L7") (pintype "passive"))
    )
    (net (code "81") (name "unconnected-(Q1E-IO_L3P_T0_DQS_PUDC_B_34-PadK7)") (class "Default")
      (node (ref "Q1") (pin "K7") (pinfunction "IO_L3P_T0_DQS_PUDC_B_34_K7") (pintype "passive"))
    )
    (net (code "82") (name "unconnected-(Q1E-IO_L4N_T0_34-PadM6)") (class "Default")
      (node (ref "Q1") (pin "M6") (pinfunction "IO_L4N_T0_34_M6") (pintype "passive"))
    )
    (net (code "83") (name "unconnected-(Q1E-IO_L4P_T0_34-PadL6)") (class "Default")
      (node (ref "Q1") (pin "L6") (pinfunction "IO_L4P_T0_34_L6") (pintype "passive"))
    )
    (net (code "84") (name "unconnected-(Q1E-IO_L5N_T0_34-PadP8)") (class "Default")
      (node (ref "Q1") (pin "P8") (pinfunction "IO_L5N_T0_34_P8") (pintype "passive"))
    )
    (net (code "85") (name "unconnected-(Q1E-IO_L5P_T0_34-PadN8)") (class "Default")
      (node (ref "Q1") (pin "N8") (pinfunction "IO_L5P_T0_34_N8") (pintype "passive"))
    )
    (net (code "86") (name "unconnected-(Q1E-IO_L6N_T0_VREF_34-PadM7)") (class "Default")
      (node (ref "Q1") (pin "M7") (pinfunction "IO_L6N_T0_VREF_34_M7") (pintype "passive"))
    )
    (net (code "87") (name "unconnected-(Q1E-IO_L6P_T0_34-PadM8)") (class "Default")
      (node (ref "Q1") (pin "M8") (pinfunction "IO_L6P_T0_34_M8") (pintype "passive"))
    )
    (net (code "88") (name "unconnected-(Q1E-IO_L7N_T1_34-PadK5)") (class "Default")
      (node (ref "Q1") (pin "K5") (pinfunction "IO_L7N_T1_34_K5") (pintype "passive"))
    )
    (net (code "89") (name "unconnected-(Q1E-IO_L7P_T1_34-PadJ5)") (class "Default")
      (node (ref "Q1") (pin "J5") (pinfunction "IO_L7P_T1_34_J5") (pintype "passive"))
    )
    (net (code "90") (name "unconnected-(Q1E-IO_L9P_T1_DQS_34-PadJ3)") (class "Default")
      (node (ref "Q1") (pin "J3") (pinfunction "IO_L9P_T1_DQS_34_J3") (pintype "passive"))
    )
    (net (code "91") (name "unconnected-(Q1E-IO_L11P_T1_SRCC_34-PadK4)") (class "Default")
      (node (ref "Q1") (pin "K4") (pinfunction "IO_L11P_T1_SRCC_34_K4") (pintype "passive"))
    )
    (net (code "92") (name "unconnected-(Q1E-IO_L12P_T1_MRCC_34-PadL5)") (class "Default")
      (node (ref "Q1") (pin "L5") (pinfunction "IO_L12P_T1_MRCC_34_L5") (pintype "passive"))
    )
    (net (code "93") (name "unconnected-(Q1E-IO_L13N_T2_MRCC_34-PadT1)") (class "Default")
      (node (ref "Q1") (pin "T1") (pinfunction "IO_L13N_T2_MRCC_34_T1") (pintype "passive"))
    )
    (net (code "94") (name "unconnected-(Q1E-IO_L14N_T2_SRCC_34-PadU1)") (class "Default")
      (node (ref "Q1") (pin "U1") (pinfunction "IO_L14N_T2_SRCC_34_U1") (pintype "passive"))
    )
    (net (code "95") (name "unconnected-(Q1E-IO_L14P_T2_SRCC_34-PadU2)") (class "Default")
      (node (ref "Q1") (pin "U2") (pinfunction "IO_L14P_T2_SRCC_34_U2") (pintype "passive"))
    )
    (net (code "96") (name "unconnected-(Q1E-IO_L16N_T2_34-PadP1)") (class "Default")
      (node (ref "Q1") (pin "P1") (pinfunction "IO_L16N_T2_34_P1") (pintype "passive"))
    )
    (net (code "97") (name "unconnected-(Q1E-IO_L17P_T2_34-PadR3)") (class "Default")
      (node (ref "Q1") (pin "R3") (pinfunction "IO_L17P_T2_34_R3") (pintype "passive"))
    )
    (net (code "98") (name "unconnected-(Q1E-IO_L19N_T3_VREF_34-PadN5)") (class "Default")
      (node (ref "Q1") (pin "N5") (pinfunction "IO_L19N_T3_VREF_34_N5") (pintype "passive"))
    )
    (net (code "99") (name "unconnected-(Q1E-IO_L19P_T3_34-PadN6)") (class "Default")
      (node (ref "Q1") (pin "N6") (pinfunction "IO_L19P_T3_34_N6") (pintype "passive"))
    )
    (net (code "100") (name "unconnected-(Q1E-IO_L20N_T3_34-PadP5)") (class "Default")
      (node (ref "Q1") (pin "P5") (pinfunction "IO_L20N_T3_34_P5") (pintype "passive"))
    )
    (net (code "101") (name "unconnected-(Q1E-IO_L20P_T3_34-PadP6)") (class "Default")
      (node (ref "Q1") (pin "P6") (pinfunction "IO_L20P_T3_34_P6") (pintype "passive"))
    )
    (net (code "102") (name "unconnected-(Q1E-IO_L21P_T3_DQS_34-PadN4)") (class "Default")
      (node (ref "Q1") (pin "N4") (pinfunction "IO_L21P_T3_DQS_34_N4") (pintype "passive"))
    )
    (net (code "103") (name "unconnected-(Q1E-IO_L23N_T3_34-PadR4)") (class "Default")
      (node (ref "Q1") (pin "R4") (pinfunction "IO_L23N_T3_34_R4") (pintype "passive"))
    )
    (net (code "104") (name "unconnected-(Q1E-IO_L23P_T3_34-PadR5)") (class "Default")
      (node (ref "Q1") (pin "R5") (pinfunction "IO_L23P_T3_34_R5") (pintype "passive"))
    )
    (net (code "105") (name "unconnected-(Q1E-IO_L24N_T3_34-PadR7)") (class "Default")
      (node (ref "Q1") (pin "R7") (pinfunction "IO_L24N_T3_34_R7") (pintype "passive"))
    )
    (net (code "106") (name "unconnected-(Q1E-IO_L24P_T3_34-PadP7)") (class "Default")
      (node (ref "Q1") (pin "P7") (pinfunction "IO_L24P_T3_34_P7") (pintype "passive"))
    )
    (net (code "107") (name "unconnected-(Q1F-IO_0_35-PadH6)") (class "Default")
      (node (ref "Q1") (pin "H6") (pinfunction "IO_0_35_H6") (pintype "passive"))
    )
    (net (code "108") (name "unconnected-(Q1F-IO_25_35-PadH5)") (class "Default")
      (node (ref "Q1") (pin "H5") (pinfunction "IO_25_35_H5") (pintype "passive"))
    )
    (net (code "109") (name "unconnected-(Q1F-IO_L1N_T0_AD0N_35-PadE7)") (class "Default")
      (node (ref "Q1") (pin "E7") (pinfunction "IO_L1N_T0_AD0N_35_E7") (pintype "passive"))
    )
    (net (code "110") (name "unconnected-(Q1F-IO_L1P_T0_AD0P_35-PadF7)") (class "Default")
      (node (ref "Q1") (pin "F7") (pinfunction "IO_L1P_T0_AD0P_35_F7") (pintype "passive"))
    )
    (net (code "111") (name "unconnected-(Q1F-IO_L2N_T0_AD8N_35-PadD6)") (class "Default")
      (node (ref "Q1") (pin "D6") (pinfunction "IO_L2N_T0_AD8N_35_D6") (pintype "passive"))
    )
    (net (code "112") (name "unconnected-(Q1F-IO_L2P_T0_AD8P_35-PadD7)") (class "Default")
      (node (ref "Q1") (pin "D7") (pinfunction "IO_L2P_T0_AD8P_35_D7") (pintype "passive"))
    )
    (net (code "113") (name "unconnected-(Q1F-IO_L3N_T0_DQS_AD1N_35-PadD8)") (class "Default")
      (node (ref "Q1") (pin "D8") (pinfunction "IO_L3N_T0_DQS_AD1N_35_D8") (pintype "passive"))
    )
    (net (code "114") (name "unconnected-(Q1F-IO_L3P_T0_DQS_AD1P_35-PadE8)") (class "Default")
      (node (ref "Q1") (pin "E8") (pinfunction "IO_L3P_T0_DQS_AD1P_35_E8") (pintype "passive"))
    )
    (net (code "115") (name "unconnected-(Q1F-IO_L4N_T0_35-PadG7)") (class "Default")
      (node (ref "Q1") (pin "G7") (pinfunction "IO_L4N_T0_35_G7") (pintype "passive"))
    )
    (net (code "116") (name "unconnected-(Q1F-IO_L4P_T0_35-PadG8)") (class "Default")
      (node (ref "Q1") (pin "G8") (pinfunction "IO_L4P_T0_35_G8") (pintype "passive"))
    )
    (net (code "117") (name "unconnected-(Q1F-IO_L5N_T0_AD9N_35-PadE5)") (class "Default")
      (node (ref "Q1") (pin "E5") (pinfunction "IO_L5N_T0_AD9N_35_E5") (pintype "passive"))
    )
    (net (code "118") (name "unconnected-(Q1F-IO_L5P_T0_AD9P_35-PadF5)") (class "Default")
      (node (ref "Q1") (pin "F5") (pinfunction "IO_L5P_T0_AD9P_35_F5") (pintype "passive"))
    )
    (net (code "119") (name "unconnected-(Q1F-IO_L6N_T0_VREF_35-PadF6)") (class "Default")
      (node (ref "Q1") (pin "F6") (pinfunction "IO_L6N_T0_VREF_35_F6") (pintype "passive"))
    )
    (net (code "120") (name "unconnected-(Q1F-IO_L6P_T0_35-PadG6)") (class "Default")
      (node (ref "Q1") (pin "G6") (pinfunction "IO_L6P_T0_35_G6") (pintype "passive"))
    )
    (net (code "121") (name "unconnected-(Q1F-IO_L7N_T1_AD2N_35-PadB8)") (class "Default")
      (node (ref "Q1") (pin "B8") (pinfunction "IO_L7N_T1_AD2N_35_B8") (pintype "passive"))
    )
    (net (code "122") (name "unconnected-(Q1F-IO_L7P_T1_AD2P_35-PadC8)") (class "Default")
      (node (ref "Q1") (pin "C8") (pinfunction "IO_L7P_T1_AD2P_35_C8") (pintype "passive"))
    )
    (net (code "123") (name "unconnected-(Q1F-IO_L8P_T1_AD10P_35-PadB7)") (class "Default")
      (node (ref "Q1") (pin "B7") (pinfunction "IO_L8P_T1_AD10P_35_B7") (pintype "passive"))
    )
    (net (code "124") (name "unconnected-(Q1F-IO_L9P_T1_DQS_AD3P_35-PadA7)") (class "Default")
      (node (ref "Q1") (pin "A7") (pinfunction "IO_L9P_T1_DQS_AD3P_35_A7") (pintype "passive"))
    )
    (net (code "125") (name "unconnected-(Q1F-IO_L12N_T1_MRCC_35-PadC4)") (class "Default")
      (node (ref "Q1") (pin "C4") (pinfunction "IO_L12N_T1_MRCC_35_C4") (pintype "passive"))
    )
    (net (code "126") (name "unconnected-(Q1F-IO_L12P_T1_MRCC_35-PadD5)") (class "Default")
      (node (ref "Q1") (pin "D5") (pinfunction "IO_L12P_T1_MRCC_35_D5") (pintype "passive"))
    )
    (net (code "127") (name "unconnected-(Q1F-IO_L19P_T3_35-PadH4)") (class "Default")
      (node (ref "Q1") (pin "H4") (pinfunction "IO_L19P_T3_35_H4") (pintype "passive"))
    )
    (net (code "128") (name "unconnected-(Q1F-IO_L20N_T3_AD6N_35-PadF4)") (class "Default")
      (node (ref "Q1") (pin "F4") (pinfunction "IO_L20N_T3_AD6N_35_F4") (pintype "passive"))
    )
    (net (code "129") (name "unconnected-(Q1F-IO_L20P_T3_AD6P_35-PadG4)") (class "Default")
      (node (ref "Q1") (pin "G4") (pinfunction "IO_L20P_T3_AD6P_35_G4") (pintype "passive"))
    )
    (net (code "130") (name "unconnected-(Q1F-IO_L22P_T3_AD7P_35-PadG3)") (class "Default")
      (node (ref "Q1") (pin "G3") (pinfunction "IO_L22P_T3_AD7P_35_G3") (pintype "passive"))
    )
    (net (code "131") (name "unconnected-(Q31-EN-Pad1)") (class "Default")
      (node (ref "Q31") (pin "1") (pinfunction "EN_1") (pintype "passive"))
    )
    (net (code "132") (name "unconnected-(Q33-INT2-Pad5)") (class "Default")
      (node (ref "Q33") (pin "5") (pinfunction "INT2_5") (pintype "passive"))
    )
  )
)
